# PLD_RadFET_LCL.net
KiCad netlist of a schematic drawn in Altium Designer
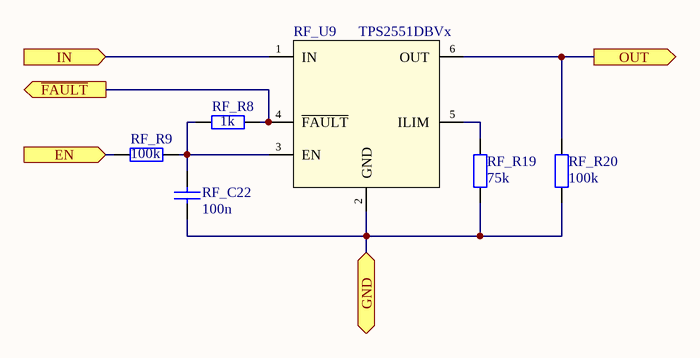
[diagram p0: PLD_RadFET_LCL.SchDoc]

(export (version "E")
  (design (tool "Eeschema 10.0.6"))
  (components
    (comp (ref "RF_C22")
      (value "100n")
      (footprint "SMD_Capacitor_0603")
      (description "Cap")
      (libsource (lib "capacitors") (part "Cap"))
    )
    (comp (ref "RF_R8")
      (value "1k")
      (footprint "SMD_Resistor_0603")
      (libsource (lib "resistors") (part "Res"))
    )
    (comp (ref "RF_R9")
      (value "100k")
      (footprint "SMD_Resistor_0603")
      (libsource (lib "resistors") (part "Res"))
    )
    (comp (ref "RF_R19") (value "75k") (footprint "SMD_Resistor_0603") (libsource (lib "") (part "Res_1")))
    (comp (ref "RF_R20") (value "100k") (footprint "SMD_Resistor_0603") (libsource (lib "") (part "Res_1")))
    (comp (ref "RF_U9")
      (value "TPS2551DBVx")
      (footprint "SOT23-6")
      (description "Adjustable Current-Limited Power-Distribution Switch.")
      (fields (field (name "MANUFACTURER") "Texas Instruments"))
      (libsource (lib "microcircuits") (part "TPS2551DBVx"))
    )
  )
  (nets
    (net (code "1") (name "/EN") (class "Default")
      (node (ref "RF_R9") (pin "2") (pinfunction "2_2") (pintype "passive"))
    )
    (net (code "2") (name "/GND") (class "Default")
      (node (ref "RF_C22") (pin "2") (pinfunction "2_2") (pintype "passive"))
      (node (ref "RF_R19") (pin "1") (pinfunction "1_1") (pintype "passive"))
      (node (ref "RF_R20") (pin "1") (pinfunction "1_1") (pintype "passive"))
      (node (ref "RF_U9") (pin "2") (pinfunction "GND_2") (pintype "passive"))
    )
    (net (code "3") (name "/IN") (class "Default")
      (node (ref "RF_U9") (pin "1") (pinfunction "IN_1") (pintype "passive"))
    )
    (net (code "4") (name "/OUT") (class "Default")
      (node (ref "RF_R20") (pin "2") (pinfunction "2_2") (pintype "passive"))
      (node (ref "RF_U9") (pin "6") (pinfunction "OUT_6") (pintype "passive"))
    )
    (net (code "5") (name "/~{FAULT}") (class "Default")
      (node (ref "RF_R8") (pin "1") (pinfunction "1_1") (pintype "passive"))
      (node (ref "RF_U9") (pin "4") (pinfunction "~{FAULT}_4") (pintype "passive"))
    )
    (net (code "6") (name "Net-(RF_U9-EN)") (class "Default")
      (node (ref "RF_C22") (pin "1") (pinfunction "1_1") (pintype "passive"))
      (node (ref "RF_R8") (pin "2") (pinfunction "2_2") (pintype "passive"))
      (node (ref "RF_R9") (pin "1") (pinfunction "1_1") (pintype "passive"))
      (node (ref "RF_U9") (pin "3") (pinfunction "EN_3") (pintype "passive"))
    )
    (net (code "7") (name "Net-(RF_U9-ILIM)") (class "Default")
      (node (ref "RF_R19") (pin "2") (pinfunction "2_2") (pintype "passive"))
      (node (ref "RF_U9") (pin "5") (pinfunction "ILIM_5") (pintype "passive"))
    )
  )
)
